# ext.net
KiCad netlist of a schematic drawn in EAGLE
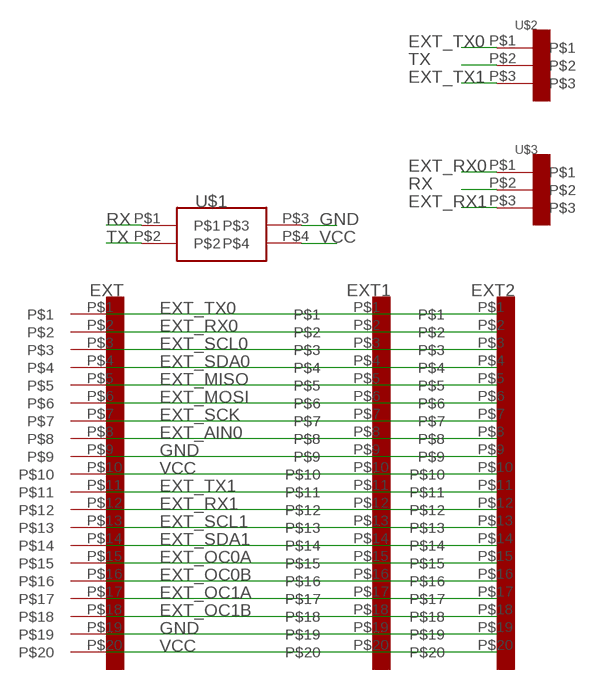
[diagram p0: schematic, sheet 1]

(export (version "E")
  (design (tool "Eeschema 10.0.6"))
  (components
    (comp (ref "EXT")
      (value "CON_DIL_20")
      (footprint "eagle-import:CON_DIL_20")
      (libsource (lib "eagle-import") (part "CON_DIL_20"))
    )
    (comp (ref "EXT1")
      (value "CON_DIL_20")
      (footprint "eagle-import:CON_DIL_20")
      (libsource (lib "eagle-import") (part "CON_DIL_20"))
    )
    (comp (ref "EXT2")
      (value "CON_DIL_20")
      (footprint "eagle-import:CON_DIL_20")
      (libsource (lib "eagle-import") (part "CON_DIL_20"))
    )
    (comp (ref "U$1")
      (value "CON_DIL_2X2")
      (footprint "eagle-import:CON_DIL_2X2")
      (libsource (lib "eagle-import") (part "CON_DIL_2X2"))
    )
    (comp (ref "U$2")
      (value "CON_DIL_3")
      (footprint "eagle-import:CON_DIL_3")
      (libsource (lib "eagle-import") (part "CON_DIL_3"))
    )
    (comp (ref "U$3")
      (value "CON_DIL_3")
      (footprint "eagle-import:CON_DIL_3")
      (libsource (lib "eagle-import") (part "CON_DIL_3"))
    )
  )
  (nets
    (net (code "1") (name "EXT_AIN0") (class "Default")
      (node (ref "EXT") (pin "P$8") (pinfunction "P$8_P$8") (pintype "bidirectional"))
      (node (ref "EXT1") (pin "P$8") (pinfunction "P$8_P$8") (pintype "bidirectional"))
      (node (ref "EXT2") (pin "P$8") (pinfunction "P$8_P$8") (pintype "bidirectional"))
    )
    (net (code "2") (name "EXT_MISO") (class "Default")
      (node (ref "EXT") (pin "P$5") (pinfunction "P$5_P$5") (pintype "bidirectional"))
      (node (ref "EXT1") (pin "P$5") (pinfunction "P$5_P$5") (pintype "bidirectional"))
      (node (ref "EXT2") (pin "P$5") (pinfunction "P$5_P$5") (pintype "bidirectional"))
    )
    (net (code "3") (name "EXT_MOSI") (class "Default")
      (node (ref "EXT") (pin "P$6") (pinfunction "P$6_P$6") (pintype "bidirectional"))
      (node (ref "EXT1") (pin "P$6") (pinfunction "P$6_P$6") (pintype "bidirectional"))
      (node (ref "EXT2") (pin "P$6") (pinfunction "P$6_P$6") (pintype "bidirectional"))
    )
    (net (code "4") (name "EXT_OC0A") (class "Default")
      (node (ref "EXT") (pin "P$15") (pinfunction "P$15_P$15") (pintype "bidirectional"))
      (node (ref "EXT1") (pin "P$15") (pinfunction "P$15_P$15") (pintype "bidirectional"))
      (node (ref "EXT2") (pin "P$15") (pinfunction "P$15_P$15") (pintype "bidirectional"))
    )
    (net (code "5") (name "EXT_OC0B") (class "Default")
      (node (ref "EXT") (pin "P$16") (pinfunction "P$16_P$16") (pintype "bidirectional"))
      (node (ref "EXT1") (pin "P$16") (pinfunction "P$16_P$16") (pintype "bidirectional"))
      (node (ref "EXT2") (pin "P$16") (pinfunction "P$16_P$16") (pintype "bidirectional"))
    )
    (net (code "6") (name "EXT_OC1A") (class "Default")
      (node (ref "EXT") (pin "P$17") (pinfunction "P$17_P$17") (pintype "bidirectional"))
      (node (ref "EXT1") (pin "P$17") (pinfunction "P$17_P$17") (pintype "bidirectional"))
      (node (ref "EXT2") (pin "P$17") (pinfunction "P$17_P$17") (pintype "bidirectional"))
    )
    (net (code "7") (name "EXT_OC1B") (class "Default")
      (node (ref "EXT") (pin "P$18") (pinfunction "P$18_P$18") (pintype "bidirectional"))
      (node (ref "EXT1") (pin "P$18") (pinfunction "P$18_P$18") (pintype "bidirectional"))
      (node (ref "EXT2") (pin "P$18") (pinfunction "P$18_P$18") (pintype "bidirectional"))
    )
    (net (code "8") (name "EXT_RX0") (class "Default")
      (node (ref "EXT") (pin "P$2") (pinfunction "P$2_P$2") (pintype "bidirectional"))
      (node (ref "EXT1") (pin "P$2") (pinfunction "P$2_P$2") (pintype "bidirectional"))
      (node (ref "EXT2") (pin "P$2") (pinfunction "P$2_P$2") (pintype "bidirectional"))
      (node (ref "U$3") (pin "P$1") (pinfunction "P$1_P$1") (pintype "bidirectional"))
    )
    (net (code "9") (name "EXT_RX1") (class "Default")
      (node (ref "EXT") (pin "P$12") (pinfunction "P$12_P$12") (pintype "bidirectional"))
      (node (ref "EXT1") (pin "P$12") (pinfunction "P$12_P$12") (pintype "bidirectional"))
      (node (ref "EXT2") (pin "P$12") (pinfunction "P$12_P$12") (pintype "bidirectional"))
      (node (ref "U$3") (pin "P$3") (pinfunction "P$3_P$3") (pintype "bidirectional"))
    )
    (net (code "10") (name "EXT_SCK") (class "Default")
      (node (ref "EXT") (pin "P$7") (pinfunction "P$7_P$7") (pintype "bidirectional"))
      (node (ref "EXT1") (pin "P$7") (pinfunction "P$7_P$7") (pintype "bidirectional"))
      (node (ref "EXT2") (pin "P$7") (pinfunction "P$7_P$7") (pintype "bidirectional"))
    )
    (net (code "11") (name "EXT_SCL0") (class "Default")
      (node (ref "EXT") (pin "P$3") (pinfunction "P$3_P$3") (pintype "bidirectional"))
      (node (ref "EXT1") (pin "P$3") (pinfunction "P$3_P$3") (pintype "bidirectional"))
      (node (ref "EXT2") (pin "P$3") (pinfunction "P$3_P$3") (pintype "bidirectional"))
    )
    (net (code "12") (name "EXT_SCL1") (class "Default")
      (node (ref "EXT") (pin "P$13") (pinfunction "P$13_P$13") (pintype "bidirectional"))
      (node (ref "EXT1") (pin "P$13") (pinfunction "P$13_P$13") (pintype "bidirectional"))
      (node (ref "EXT2") (pin "P$13") (pinfunction "P$13_P$13") (pintype "bidirectional"))
    )
    (net (code "13") (name "EXT_SDA0") (class "Default")
      (node (ref "EXT") (pin "P$4") (pinfunction "P$4_P$4") (pintype "bidirectional"))
      (node (ref "EXT1") (pin "P$4") (pinfunction "P$4_P$4") (pintype "bidirectional"))
      (node (ref "EXT2") (pin "P$4") (pinfunction "P$4_P$4") (pintype "bidirectional"))
    )
    (net (code "14") (name "EXT_SDA1") (class "Default")
      (node (ref "EXT") (pin "P$14") (pinfunction "P$14_P$14") (pintype "bidirectional"))
      (node (ref "EXT1") (pin "P$14") (pinfunction "P$14_P$14") (pintype "bidirectional"))
      (node (ref "EXT2") (pin "P$14") (pinfunction "P$14_P$14") (pintype "bidirectional"))
    )
    (net (code "15") (name "EXT_TX0") (class "Default")
      (node (ref "EXT") (pin "P$1") (pinfunction "P$1_P$1") (pintype "bidirectional"))
      (node (ref "EXT1") (pin "P$1") (pinfunction "P$1_P$1") (pintype "bidirectional"))
      (node (ref "EXT2") (pin "P$1") (pinfunction "P$1_P$1") (pintype "bidirectional"))
      (node (ref "U$2") (pin "P$1") (pinfunction "P$1_P$1") (pintype "bidirectional"))
    )
    (net (code "16") (name "EXT_TX1") (class "Default")
      (node (ref "EXT") (pin "P$11") (pinfunction "P$11_P$11") (pintype "bidirectional"))
      (node (ref "EXT1") (pin "P$11") (pinfunction "P$11_P$11") (pintype "bidirectional"))
      (node (ref "EXT2") (pin "P$11") (pinfunction "P$11_P$11") (pintype "bidirectional"))
      (node (ref "U$2") (pin "P$3") (pinfunction "P$3_P$3") (pintype "bidirectional"))
    )
    (net (code "17") (name "GND") (class "Default")
      (node (ref "EXT") (pin "P$19") (pinfunction "P$19_P$19") (pintype "bidirectional"))
      (node (ref "EXT") (pin "P$9") (pinfunction "P$9_P$9") (pintype "bidirectional"))
      (node (ref "EXT1") (pin "P$19") (pinfunction "P$19_P$19") (pintype "bidirectional"))
      (node (ref "EXT1") (pin "P$9") (pinfunction "P$9_P$9") (pintype "bidirectional"))
      (node (ref "EXT2") (pin "P$19") (pinfunction "P$19_P$19") (pintype "bidirectional"))
      (node (ref "EXT2") (pin "P$9") (pinfunction "P$9_P$9") (pintype "bidirectional"))
      (node (ref "U$1") (pin "P$3") (pinfunction "P$3_P$3") (pintype "bidirectional"))
    )
    (net (code "18") (name "RX") (class "Default")
      (node (ref "U$1") (pin "P$1") (pinfunction "P$1_P$1") (pintype "bidirectional"))
      (node (ref "U$3") (pin "P$2") (pinfunction "P$2_P$2") (pintype "bidirectional"))
    )
    (net (code "19") (name "TX") (class "Default")
      (node (ref "U$1") (pin "P$2") (pinfunction "P$2_P$2") (pintype "bidirectional"))
      (node (ref "U$2") (pin "P$2") (pinfunction "P$2_P$2") (pintype "bidirectional"))
    )
    (net (code "20") (name "VCC") (class "Default")
      (node (ref "EXT") (pin "P$10") (pinfunction "P$10_P$10") (pintype "bidirectional"))
      (node (ref "EXT") (pin "P$20") (pinfunction "P$20_P$20") (pintype "bidirectional"))
      (node (ref "EXT1") (pin "P$10") (pinfunction "P$10_P$10") (pintype "bidirectional"))
      (node (ref "EXT1") (pin "P$20") (pinfunction "P$20_P$20") (pintype "bidirectional"))
      (node (ref "EXT2") (pin "P$10") (pinfunction "P$10_P$10") (pintype "bidirectional"))
      (node (ref "EXT2") (pin "P$20") (pinfunction "P$20_P$20") (pintype "bidirectional"))
      (node (ref "U$1") (pin "P$4") (pinfunction "P$4_P$4") (pintype "bidirectional"))
    )
  )
)
